# rapidshark-display-butt-mk-1_0.net
KiCad netlist of a schematic drawn in EAGLE
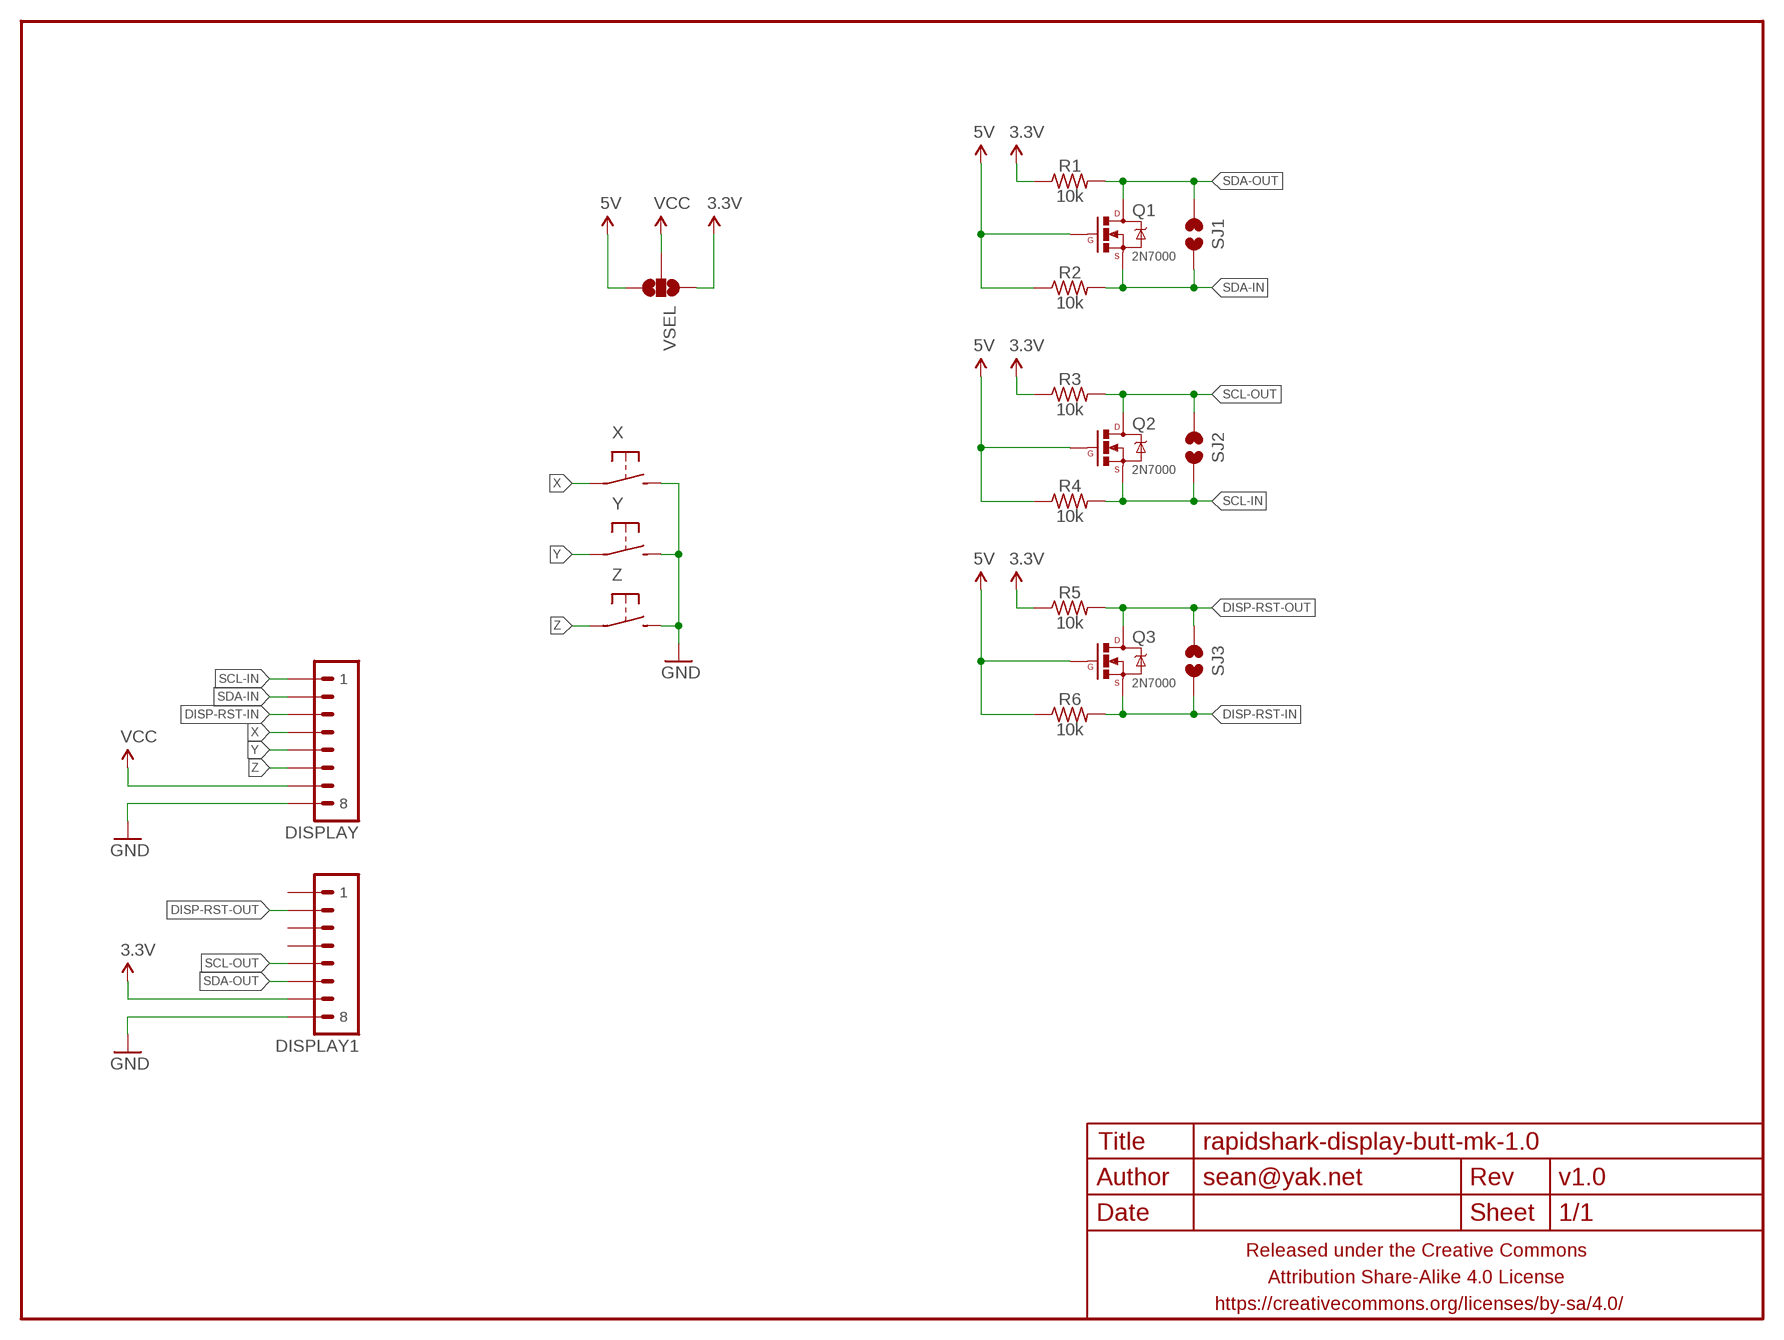
[diagram p0: schematic, sheet 1]

(export (version "E")
  (design (tool "Eeschema 10.0.6"))
  (components
    (comp (ref "DISPLAY")
      (value "M08JST-PH-VERT-PTH")
      (footprint "eagle-import:JST-8-VERT-PTH")
      (libsource (lib "eagle-import") (part "M08JST-PH-VERT-PTH"))
    )
    (comp (ref "DISPLAY1")
      (value "M081X08")
      (footprint "eagle-import:1X08")
      (libsource (lib "eagle-import") (part "M081X08"))
    )
    (comp (ref "FRAME1")
      (value "FRAME-LETTERNO_PACKAGE")
      (footprint "eagle-import:DUMMY")
      (fields (field (name "DESIGNER") "sean@yak.net") (field (name "VERSION") "v1.0"))
      (libsource (lib "eagle-import") (part "FRAME-LETTERNO_PACKAGE"))
    )
    (comp (ref "Q1")
      (value "2N7000")
      (footprint "eagle-import:TO-92-AMMO")
      (libsource (lib "eagle-import") (part "MOSFET-NCHANNEL2N7000-AMMO"))
    )
    (comp (ref "Q2")
      (value "2N7000")
      (footprint "eagle-import:TO-92-AMMO")
      (libsource (lib "eagle-import") (part "MOSFET-NCHANNEL2N7000-AMMO"))
    )
    (comp (ref "Q3")
      (value "2N7000")
      (footprint "eagle-import:TO-92-AMMO")
      (libsource (lib "eagle-import") (part "MOSFET-NCHANNEL2N7000-AMMO"))
    )
    (comp (ref "R1")
      (value "10k")
      (footprint "eagle-import:RESISTOR-AXIAL-PTH-5.08MM")
      (libsource (lib "eagle-import") (part "RESISTORPTH-AXIAL-5.08MM"))
    )
    (comp (ref "R2")
      (value "10k")
      (footprint "eagle-import:RESISTOR-AXIAL-PTH-5.08MM")
      (libsource (lib "eagle-import") (part "RESISTORPTH-AXIAL-5.08MM"))
    )
    (comp (ref "R3")
      (value "10k")
      (footprint "eagle-import:RESISTOR-AXIAL-PTH-5.08MM")
      (libsource (lib "eagle-import") (part "RESISTORPTH-AXIAL-5.08MM"))
    )
    (comp (ref "R4")
      (value "10k")
      (footprint "eagle-import:RESISTOR-AXIAL-PTH-5.08MM")
      (libsource (lib "eagle-import") (part "RESISTORPTH-AXIAL-5.08MM"))
    )
    (comp (ref "R5")
      (value "10k")
      (footprint "eagle-import:RESISTOR-AXIAL-PTH-5.08MM")
      (libsource (lib "eagle-import") (part "RESISTORPTH-AXIAL-5.08MM"))
    )
    (comp (ref "R6")
      (value "10k")
      (footprint "eagle-import:RESISTOR-AXIAL-PTH-5.08MM")
      (libsource (lib "eagle-import") (part "RESISTORPTH-AXIAL-5.08MM"))
    )
    (comp (ref "SJ1")
      (value "JUMPER-PAD-2-NOYES_SILK")
      (footprint "eagle-import:PAD-JUMPER-2-NO_YES_SILK")
      (libsource (lib "eagle-import") (part "JUMPER-PAD-2-NOYES_SILK"))
    )
    (comp (ref "SJ2")
      (value "JUMPER-PAD-2-NOYES_SILK")
      (footprint "eagle-import:PAD-JUMPER-2-NO_YES_SILK")
      (libsource (lib "eagle-import") (part "JUMPER-PAD-2-NOYES_SILK"))
    )
    (comp (ref "SJ3")
      (value "JUMPER-PAD-2-NOYES_SILK")
      (footprint "eagle-import:PAD-JUMPER-2-NO_YES_SILK")
      (libsource (lib "eagle-import") (part "JUMPER-PAD-2-NOYES_SILK"))
    )
    (comp (ref "VSEL")
      (value "JUMPER-PAD-3-NOFULL_BOX_SILK")
      (footprint "eagle-import:PAD-JUMPER-3-NO_YES_SILK_FULL_BOX")
      (libsource (lib "eagle-import") (part "JUMPER-PAD-3-NOFULL_BOX_SILK"))
    )
    (comp (ref "X")
      (value "SPST-NO-TACT6MM-PTH-SMALL-PADS")
      (footprint "eagle-import:DTS-6-SMALL-PADS")
      (libsource (lib "eagle-import") (part "SPST-NO-TACT6MM-PTH-SMALL-PADS"))
    )
    (comp (ref "Y")
      (value "SPST-NO-TACT6MM-PTH-SMALL-PADS")
      (footprint "eagle-import:DTS-6-SMALL-PADS")
      (libsource (lib "eagle-import") (part "SPST-NO-TACT6MM-PTH-SMALL-PADS"))
    )
    (comp (ref "Z")
      (value "SPST-NO-TACT6MM-PTH-SMALL-PADS")
      (footprint "eagle-import:DTS-6-SMALL-PADS")
      (libsource (lib "eagle-import") (part "SPST-NO-TACT6MM-PTH-SMALL-PADS"))
    )
  )
  (nets
    (net (code "1") (name "3.3V") (class "Default")
      (node (ref "DISPLAY1") (pin "7") (pinfunction "7_7") (pintype "passive"))
      (node (ref "R1") (pin "P$1") (pinfunction "1_P$1") (pintype "passive"))
      (node (ref "R3") (pin "P$1") (pinfunction "1_P$1") (pintype "passive"))
      (node (ref "R5") (pin "P$1") (pinfunction "1_P$1") (pintype "passive"))
      (node (ref "VSEL") (pin "1") (pinfunction "1_1") (pintype "passive"))
    )
    (net (code "2") (name "5V") (class "Default")
      (node (ref "Q1") (pin "2") (pinfunction "G_2") (pintype "passive"))
      (node (ref "Q2") (pin "2") (pinfunction "G_2") (pintype "passive"))
      (node (ref "Q3") (pin "2") (pinfunction "G_2") (pintype "passive"))
      (node (ref "R2") (pin "P$1") (pinfunction "1_P$1") (pintype "passive"))
      (node (ref "R4") (pin "P$1") (pinfunction "1_P$1") (pintype "passive"))
      (node (ref "R6") (pin "P$1") (pinfunction "1_P$1") (pintype "passive"))
      (node (ref "VSEL") (pin "3") (pinfunction "3_3") (pintype "passive"))
    )
    (net (code "3") (name "DISP-RST-IN") (class "Default")
      (node (ref "DISPLAY") (pin "3") (pinfunction "3_3") (pintype "passive"))
      (node (ref "Q3") (pin "1") (pinfunction "S_1") (pintype "passive"))
      (node (ref "R6") (pin "P$2") (pinfunction "2_P$2") (pintype "passive"))
      (node (ref "SJ3") (pin "1") (pinfunction "1_1") (pintype "passive"))
    )
    (net (code "4") (name "DISP-RST-OUT") (class "Default")
      (node (ref "DISPLAY1") (pin "2") (pinfunction "2_2") (pintype "passive"))
      (node (ref "Q3") (pin "3") (pinfunction "D_3") (pintype "passive"))
      (node (ref "R5") (pin "P$2") (pinfunction "2_P$2") (pintype "passive"))
      (node (ref "SJ3") (pin "2") (pinfunction "2_2") (pintype "passive"))
    )
    (net (code "5") (name "GND") (class "Default")
      (node (ref "DISPLAY") (pin "8") (pinfunction "8_8") (pintype "passive"))
      (node (ref "DISPLAY1") (pin "8") (pinfunction "8_8") (pintype "passive"))
      (node (ref "X") (pin "3") (pinfunction "2_3") (pintype "passive"))
      (node (ref "X") (pin "4") (pinfunction "2_4") (pintype "passive"))
      (node (ref "Y") (pin "3") (pinfunction "2_3") (pintype "passive"))
      (node (ref "Y") (pin "4") (pinfunction "2_4") (pintype "passive"))
      (node (ref "Z") (pin "3") (pinfunction "2_3") (pintype "passive"))
      (node (ref "Z") (pin "4") (pinfunction "2_4") (pintype "passive"))
    )
    (net (code "6") (name "SCL-IN") (class "Default")
      (node (ref "DISPLAY") (pin "1") (pinfunction "1_1") (pintype "passive"))
      (node (ref "Q2") (pin "1") (pinfunction "S_1") (pintype "passive"))
      (node (ref "R4") (pin "P$2") (pinfunction "2_P$2") (pintype "passive"))
      (node (ref "SJ2") (pin "1") (pinfunction "1_1") (pintype "passive"))
    )
    (net (code "7") (name "SCL-OUT") (class "Default")
      (node (ref "DISPLAY1") (pin "5") (pinfunction "5_5") (pintype "passive"))
      (node (ref "Q2") (pin "3") (pinfunction "D_3") (pintype "passive"))
      (node (ref "R3") (pin "P$2") (pinfunction "2_P$2") (pintype "passive"))
      (node (ref "SJ2") (pin "2") (pinfunction "2_2") (pintype "passive"))
    )
    (net (code "8") (name "SDA-IN") (class "Default")
      (node (ref "DISPLAY") (pin "2") (pinfunction "2_2") (pintype "passive"))
      (node (ref "Q1") (pin "1") (pinfunction "S_1") (pintype "passive"))
      (node (ref "R2") (pin "P$2") (pinfunction "2_P$2") (pintype "passive"))
      (node (ref "SJ1") (pin "1") (pinfunction "1_1") (pintype "passive"))
    )
    (net (code "9") (name "SDA-OUT") (class "Default")
      (node (ref "DISPLAY1") (pin "6") (pinfunction "6_6") (pintype "passive"))
      (node (ref "Q1") (pin "3") (pinfunction "D_3") (pintype "passive"))
      (node (ref "R1") (pin "P$2") (pinfunction "2_P$2") (pintype "passive"))
      (node (ref "SJ1") (pin "2") (pinfunction "2_2") (pintype "passive"))
    )
    (net (code "10") (name "VCC") (class "Default")
      (node (ref "DISPLAY") (pin "7") (pinfunction "7_7") (pintype "passive"))
      (node (ref "VSEL") (pin "2") (pinfunction "2_2") (pintype "passive"))
    )
    (net (code "11") (name "X") (class "Default")
      (node (ref "DISPLAY") (pin "4") (pinfunction "4_4") (pintype "passive"))
      (node (ref "X") (pin "1") (pinfunction "1_1") (pintype "passive"))
      (node (ref "X") (pin "2") (pinfunction "1_2") (pintype "passive"))
    )
    (net (code "12") (name "Y") (class "Default")
      (node (ref "DISPLAY") (pin "5") (pinfunction "5_5") (pintype "passive"))
      (node (ref "Y") (pin "1") (pinfunction "1_1") (pintype "passive"))
      (node (ref "Y") (pin "2") (pinfunction "1_2") (pintype "passive"))
    )
    (net (code "13") (name "Z") (class "Default")
      (node (ref "DISPLAY") (pin "6") (pinfunction "6_6") (pintype "passive"))
      (node (ref "Z") (pin "1") (pinfunction "1_1") (pintype "passive"))
      (node (ref "Z") (pin "2") (pinfunction "1_2") (pintype "passive"))
    )
    (net (code "14") (name "unconnected-(DISPLAY1-Pad1)") (class "Default")
      (node (ref "DISPLAY1") (pin "1") (pinfunction "1_1") (pintype "passive"))
    )
    (net (code "15") (name "unconnected-(DISPLAY1-Pad3)") (class "Default")
      (node (ref "DISPLAY1") (pin "3") (pinfunction "3_3") (pintype "passive"))
    )
    (net (code "16") (name "unconnected-(DISPLAY1-Pad4)") (class "Default")
      (node (ref "DISPLAY1") (pin "4") (pinfunction "4_4") (pintype "passive"))
    )
  )
)
